# matrix.net
KiCad netlist of a schematic drawn in EAGLE
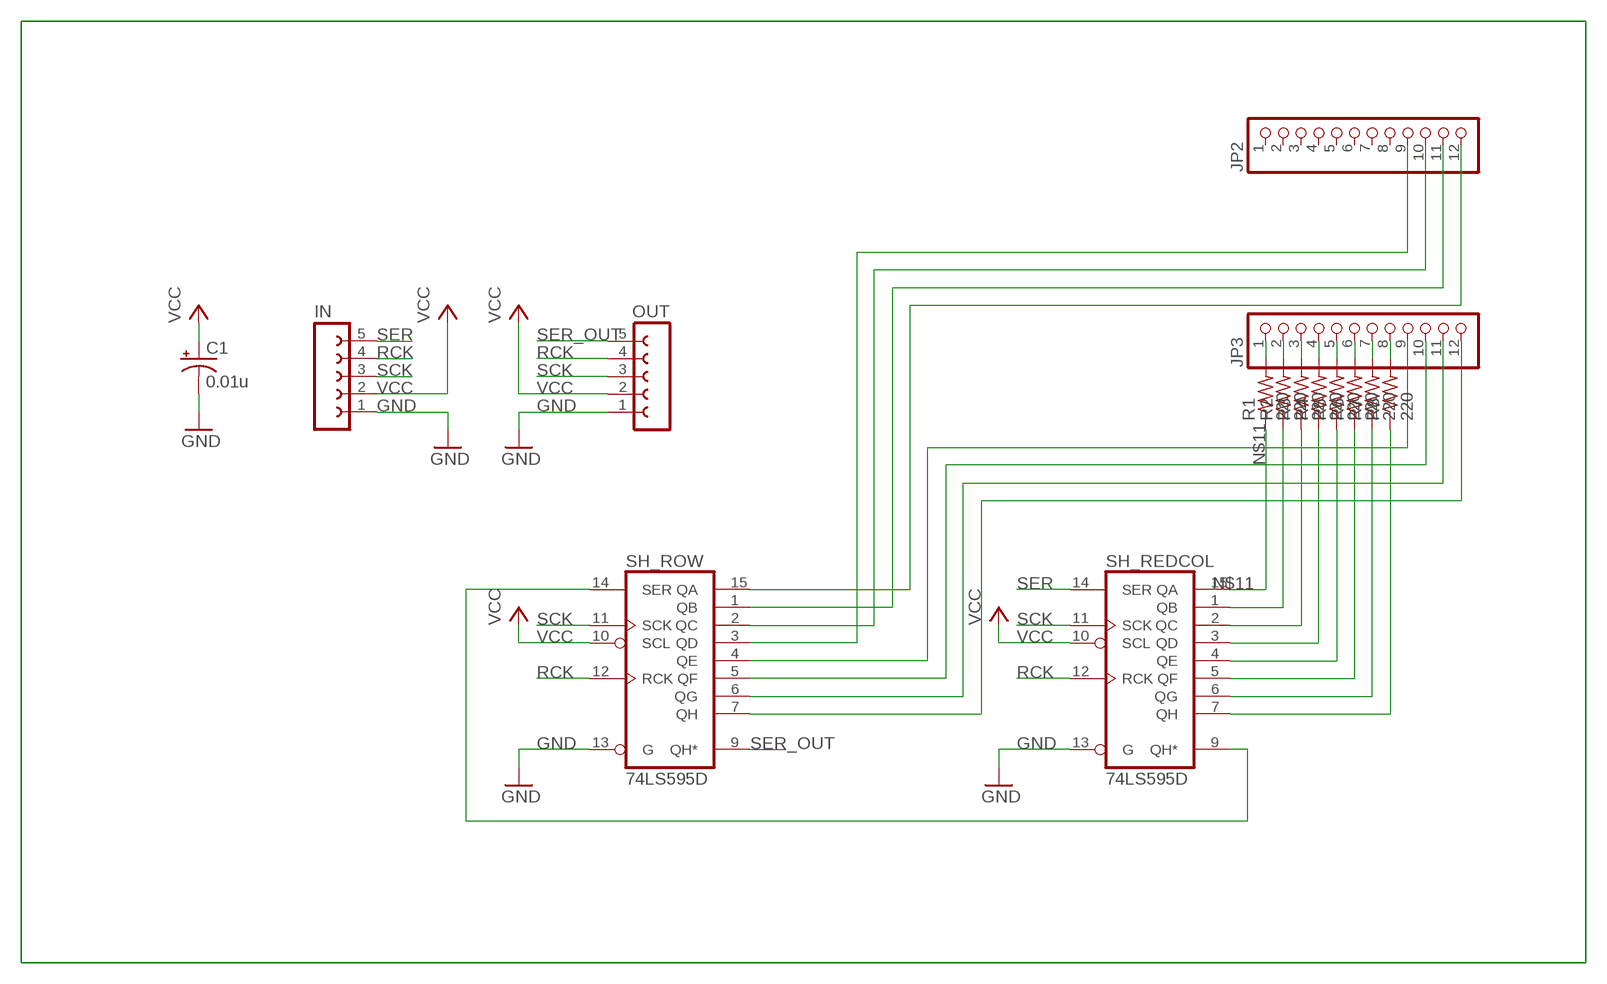
[diagram p0: schematic, sheet 1]

(export (version "E")
  (design (tool "Eeschema 10.0.6"))
  (components
    (comp (ref "C1")
      (value "0.01u")
      (footprint "eagle-import:E2,5-5")
      (libsource (lib "eagle-import") (part "CPOL-USE2.5-5"))
    )
    (comp (ref "IN")
      (value "FE05W")
      (footprint "eagle-import:FE05W")
      (libsource (lib "eagle-import") (part "FE05W"))
    )
    (comp (ref "JP2")
      (value "PINHD-1X12-CB")
      (footprint "eagle-import:1X12-CB")
      (libsource (lib "eagle-import") (part "PINHD-1X12-CB"))
    )
    (comp (ref "JP3")
      (value "PINHD-1X12-CB")
      (footprint "eagle-import:1X12-CB")
      (libsource (lib "eagle-import") (part "PINHD-1X12-CB"))
    )
    (comp (ref "OUT")
      (value "FE05W")
      (footprint "eagle-import:FE05W")
      (libsource (lib "eagle-import") (part "FE05W"))
    )
    (comp (ref "R1")
      (value "220")
      (footprint "eagle-import:R0603")
      (libsource (lib "eagle-import") (part "R-US_R0603"))
    )
    (comp (ref "R2")
      (value "220")
      (footprint "eagle-import:R0603")
      (libsource (lib "eagle-import") (part "R-US_R0603"))
    )
    (comp (ref "R3")
      (value "220")
      (footprint "eagle-import:R0603")
      (libsource (lib "eagle-import") (part "R-US_R0603"))
    )
    (comp (ref "R4")
      (value "220")
      (footprint "eagle-import:R0603")
      (libsource (lib "eagle-import") (part "R-US_R0603"))
    )
    (comp (ref "R5")
      (value "220")
      (footprint "eagle-import:R0603")
      (libsource (lib "eagle-import") (part "R-US_R0603"))
    )
    (comp (ref "R6")
      (value "220")
      (footprint "eagle-import:R0603")
      (libsource (lib "eagle-import") (part "R-US_R0603"))
    )
    (comp (ref "R7")
      (value "220")
      (footprint "eagle-import:R0603")
      (libsource (lib "eagle-import") (part "R-US_R0603"))
    )
    (comp (ref "R8")
      (value "220")
      (footprint "eagle-import:R0603")
      (libsource (lib "eagle-import") (part "R-US_R0603"))
    )
    (comp (ref "SH_REDCOL")
      (value "74LS595D")
      (footprint "eagle-import:SO16")
      (libsource (lib "eagle-import") (part "74595DLS"))
    )
    (comp (ref "SH_ROW")
      (value "74LS595D")
      (footprint "eagle-import:SO16")
      (libsource (lib "eagle-import") (part "74595DLS"))
    )
  )
  (nets
    (net (code "1") (name "/N$11") (class "Default")
      (node (ref "R1") (pin "1") (pinfunction "1_1") (pintype "passive"))
      (node (ref "SH_REDCOL") (pin "15") (pinfunction "QA_15") (pintype "tri_state"))
    )
    (net (code "2") (name "/RCK") (class "Default")
      (node (ref "IN") (pin "4") (pinfunction "4_4") (pintype "passive"))
      (node (ref "OUT") (pin "4") (pinfunction "4_4") (pintype "passive"))
      (node (ref "SH_REDCOL") (pin "12") (pinfunction "RCK_12") (pintype "input"))
      (node (ref "SH_ROW") (pin "12") (pinfunction "RCK_12") (pintype "input"))
    )
    (net (code "3") (name "/SCK") (class "Default")
      (node (ref "IN") (pin "3") (pinfunction "3_3") (pintype "passive"))
      (node (ref "OUT") (pin "3") (pinfunction "3_3") (pintype "passive"))
      (node (ref "SH_REDCOL") (pin "11") (pinfunction "SCK_11") (pintype "input"))
      (node (ref "SH_ROW") (pin "11") (pinfunction "SCK_11") (pintype "input"))
    )
    (net (code "4") (name "/SER") (class "Default")
      (node (ref "IN") (pin "5") (pinfunction "5_5") (pintype "passive"))
      (node (ref "SH_REDCOL") (pin "14") (pinfunction "SER_14") (pintype "input"))
    )
    (net (code "5") (name "/SER_OUT") (class "Default")
      (node (ref "OUT") (pin "5") (pinfunction "5_5") (pintype "passive"))
      (node (ref "SH_ROW") (pin "9") (pinfunction "QH*_9") (pintype "tri_state"))
    )
    (net (code "6") (name "GND") (class "Default")
      (node (ref "C1") (pin "-") (pinfunction "-_-") (pintype "passive"))
      (node (ref "IN") (pin "1") (pinfunction "1_1") (pintype "passive"))
      (node (ref "OUT") (pin "1") (pinfunction "1_1") (pintype "passive"))
      (node (ref "SH_REDCOL") (pin "13") (pinfunction "G_13") (pintype "input"))
      (node (ref "SH_ROW") (pin "13") (pinfunction "G_13") (pintype "input"))
    )
    (net (code "7") (name "Net-(JP3-Pad1)") (class "Default")
      (node (ref "JP3") (pin "1") (pinfunction "1_1") (pintype "passive"))
      (node (ref "R1") (pin "2") (pinfunction "2_2") (pintype "passive"))
    )
    (net (code "8") (name "Net-(JP3-Pad2)") (class "Default")
      (node (ref "JP3") (pin "2") (pinfunction "2_2") (pintype "passive"))
      (node (ref "R2") (pin "2") (pinfunction "2_2") (pintype "passive"))
    )
    (net (code "9") (name "Net-(JP3-Pad3)") (class "Default")
      (node (ref "JP3") (pin "3") (pinfunction "3_3") (pintype "passive"))
      (node (ref "R3") (pin "2") (pinfunction "2_2") (pintype "passive"))
    )
    (net (code "10") (name "Net-(JP3-Pad4)") (class "Default")
      (node (ref "JP3") (pin "4") (pinfunction "4_4") (pintype "passive"))
      (node (ref "R4") (pin "2") (pinfunction "2_2") (pintype "passive"))
    )
    (net (code "11") (name "Net-(JP3-Pad5)") (class "Default")
      (node (ref "JP3") (pin "5") (pinfunction "5_5") (pintype "passive"))
      (node (ref "R5") (pin "2") (pinfunction "2_2") (pintype "passive"))
    )
    (net (code "12") (name "Net-(JP3-Pad6)") (class "Default")
      (node (ref "JP3") (pin "6") (pinfunction "6_6") (pintype "passive"))
      (node (ref "R6") (pin "2") (pinfunction "2_2") (pintype "passive"))
    )
    (net (code "13") (name "Net-(JP3-Pad7)") (class "Default")
      (node (ref "JP3") (pin "7") (pinfunction "7_7") (pintype "passive"))
      (node (ref "R7") (pin "2") (pinfunction "2_2") (pintype "passive"))
    )
    (net (code "14") (name "Net-(JP3-Pad8)") (class "Default")
      (node (ref "JP3") (pin "8") (pinfunction "8_8") (pintype "passive"))
      (node (ref "R8") (pin "2") (pinfunction "2_2") (pintype "passive"))
    )
    (net (code "15") (name "Net-(SH_REDCOLA-QB)") (class "Default")
      (node (ref "R2") (pin "1") (pinfunction "1_1") (pintype "passive"))
      (node (ref "SH_REDCOL") (pin "1") (pinfunction "QB_1") (pintype "tri_state"))
    )
    (net (code "16") (name "Net-(SH_REDCOLA-QC)") (class "Default")
      (node (ref "R3") (pin "1") (pinfunction "1_1") (pintype "passive"))
      (node (ref "SH_REDCOL") (pin "2") (pinfunction "QC_2") (pintype "tri_state"))
    )
    (net (code "17") (name "Net-(SH_REDCOLA-QD)") (class "Default")
      (node (ref "R4") (pin "1") (pinfunction "1_1") (pintype "passive"))
      (node (ref "SH_REDCOL") (pin "3") (pinfunction "QD_3") (pintype "tri_state"))
    )
    (net (code "18") (name "Net-(SH_REDCOLA-QE)") (class "Default")
      (node (ref "R5") (pin "1") (pinfunction "1_1") (pintype "passive"))
      (node (ref "SH_REDCOL") (pin "4") (pinfunction "QE_4") (pintype "tri_state"))
    )
    (net (code "19") (name "Net-(SH_REDCOLA-QF)") (class "Default")
      (node (ref "R6") (pin "1") (pinfunction "1_1") (pintype "passive"))
      (node (ref "SH_REDCOL") (pin "5") (pinfunction "QF_5") (pintype "tri_state"))
    )
    (net (code "20") (name "Net-(SH_REDCOLA-QG)") (class "Default")
      (node (ref "R7") (pin "1") (pinfunction "1_1") (pintype "passive"))
      (node (ref "SH_REDCOL") (pin "6") (pinfunction "QG_6") (pintype "tri_state"))
    )
    (net (code "21") (name "Net-(SH_REDCOLA-QH)") (class "Default")
      (node (ref "R8") (pin "1") (pinfunction "1_1") (pintype "passive"))
      (node (ref "SH_REDCOL") (pin "7") (pinfunction "QH_7") (pintype "tri_state"))
    )
    (net (code "22") (name "Net-(SH_REDCOLA-QH*)") (class "Default")
      (node (ref "SH_REDCOL") (pin "9") (pinfunction "QH*_9") (pintype "tri_state"))
      (node (ref "SH_ROW") (pin "14") (pinfunction "SER_14") (pintype "input"))
    )
    (net (code "23") (name "Net-(SH_ROWA-QA)") (class "Default")
      (node (ref "JP2") (pin "12") (pinfunction "12_12") (pintype "passive"))
      (node (ref "SH_ROW") (pin "15") (pinfunction "QA_15") (pintype "tri_state"))
    )
    (net (code "24") (name "Net-(SH_ROWA-QB)") (class "Default")
      (node (ref "JP2") (pin "11") (pinfunction "11_11") (pintype "passive"))
      (node (ref "SH_ROW") (pin "1") (pinfunction "QB_1") (pintype "tri_state"))
    )
    (net (code "25") (name "Net-(SH_ROWA-QC)") (class "Default")
      (node (ref "JP2") (pin "10") (pinfunction "10_10") (pintype "passive"))
      (node (ref "SH_ROW") (pin "2") (pinfunction "QC_2") (pintype "tri_state"))
    )
    (net (code "26") (name "Net-(SH_ROWA-QD)") (class "Default")
      (node (ref "JP2") (pin "9") (pinfunction "9_9") (pintype "passive"))
      (node (ref "SH_ROW") (pin "3") (pinfunction "QD_3") (pintype "tri_state"))
    )
    (net (code "27") (name "Net-(SH_ROWA-QE)") (class "Default")
      (node (ref "JP3") (pin "9") (pinfunction "9_9") (pintype "passive"))
      (node (ref "SH_ROW") (pin "4") (pinfunction "QE_4") (pintype "tri_state"))
    )
    (net (code "28") (name "Net-(SH_ROWA-QF)") (class "Default")
      (node (ref "JP3") (pin "10") (pinfunction "10_10") (pintype "passive"))
      (node (ref "SH_ROW") (pin "5") (pinfunction "QF_5") (pintype "tri_state"))
    )
    (net (code "29") (name "Net-(SH_ROWA-QG)") (class "Default")
      (node (ref "JP3") (pin "11") (pinfunction "11_11") (pintype "passive"))
      (node (ref "SH_ROW") (pin "6") (pinfunction "QG_6") (pintype "tri_state"))
    )
    (net (code "30") (name "Net-(SH_ROWA-QH)") (class "Default")
      (node (ref "JP3") (pin "12") (pinfunction "12_12") (pintype "passive"))
      (node (ref "SH_ROW") (pin "7") (pinfunction "QH_7") (pintype "tri_state"))
    )
    (net (code "31") (name "VCC") (class "Default")
      (node (ref "C1") (pin "+") (pinfunction "+_+") (pintype "passive"))
      (node (ref "IN") (pin "2") (pinfunction "2_2") (pintype "passive"))
      (node (ref "OUT") (pin "2") (pinfunction "2_2") (pintype "passive"))
      (node (ref "SH_REDCOL") (pin "10") (pinfunction "SCL_10") (pintype "input"))
      (node (ref "SH_ROW") (pin "10") (pinfunction "SCL_10") (pintype "input"))
    )
    (net (code "32") (name "unconnected-(JP2-Pad1)") (class "Default")
      (node (ref "JP2") (pin "1") (pinfunction "1_1") (pintype "passive"))
    )
    (net (code "33") (name "unconnected-(JP2-Pad2)") (class "Default")
      (node (ref "JP2") (pin "2") (pinfunction "2_2") (pintype "passive"))
    )
    (net (code "34") (name "unconnected-(JP2-Pad3)") (class "Default")
      (node (ref "JP2") (pin "3") (pinfunction "3_3") (pintype "passive"))
    )
    (net (code "35") (name "unconnected-(JP2-Pad4)") (class "Default")
      (node (ref "JP2") (pin "4") (pinfunction "4_4") (pintype "passive"))
    )
    (net (code "36") (name "unconnected-(JP2-Pad5)") (class "Default")
      (node (ref "JP2") (pin "5") (pinfunction "5_5") (pintype "passive"))
    )
    (net (code "37") (name "unconnected-(JP2-Pad6)") (class "Default")
      (node (ref "JP2") (pin "6") (pinfunction "6_6") (pintype "passive"))
    )
    (net (code "38") (name "unconnected-(JP2-Pad7)") (class "Default")
      (node (ref "JP2") (pin "7") (pinfunction "7_7") (pintype "passive"))
    )
    (net (code "39") (name "unconnected-(JP2-Pad8)") (class "Default")
      (node (ref "JP2") (pin "8") (pinfunction "8_8") (pintype "passive"))
    )
  )
)
